# MainInterfaceBoard.net
KiCad netlist of a schematic drawn in EAGLE
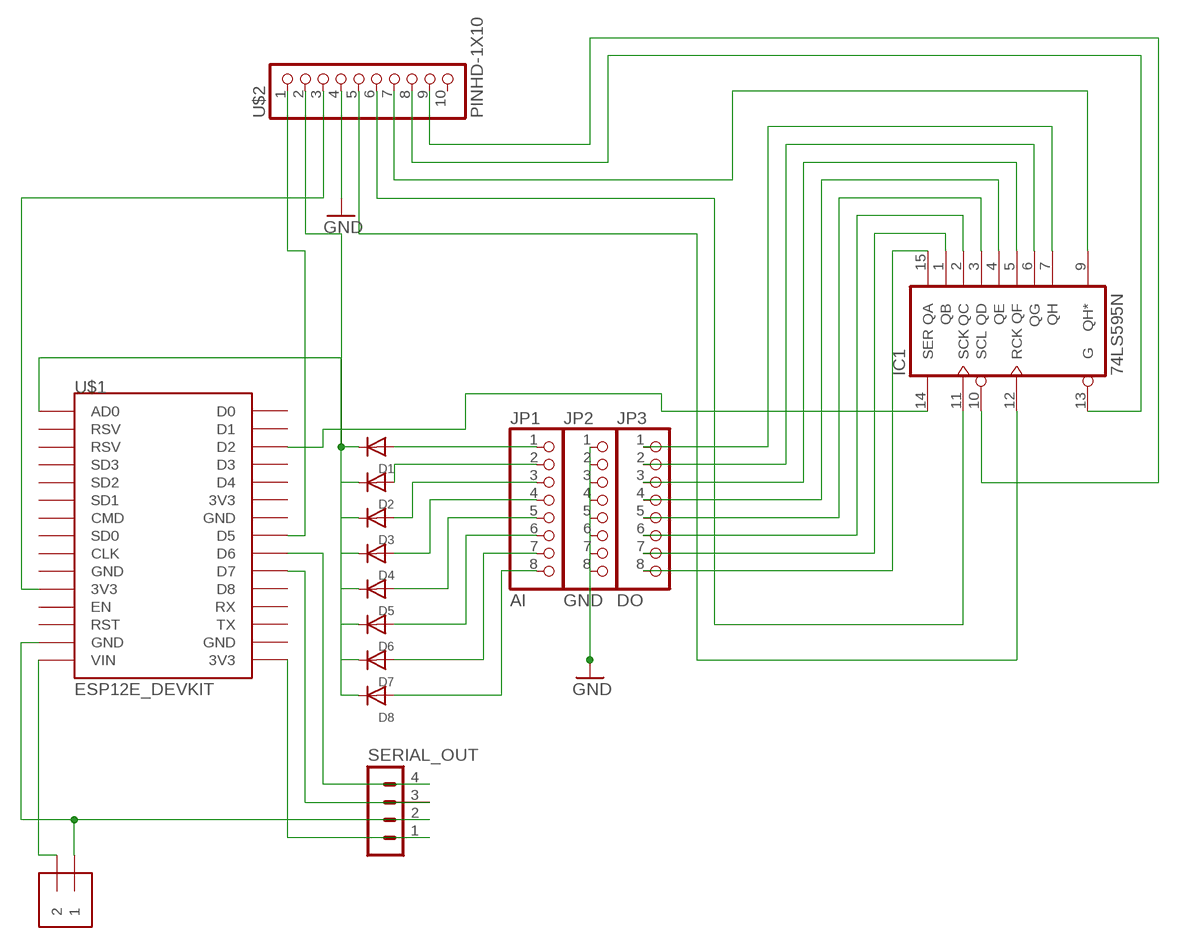
[diagram p0: schematic, sheet 1]

(export (version "E")
  (design (tool "Eeschema 10.0.6"))
  (components
    (comp (ref "D1")
      (value "DIODEDO-1N4148")
      (footprint "eagle-import:DO-1N4148")
      (libsource (lib "eagle-import") (part "DIODEDO-1N4148"))
    )
    (comp (ref "D2")
      (value "DIODEDO-1N4148")
      (footprint "eagle-import:DO-1N4148")
      (libsource (lib "eagle-import") (part "DIODEDO-1N4148"))
    )
    (comp (ref "D3")
      (value "DIODEDO-1N4148")
      (footprint "eagle-import:DO-1N4148")
      (libsource (lib "eagle-import") (part "DIODEDO-1N4148"))
    )
    (comp (ref "D4")
      (value "DIODEDO-1N4148")
      (footprint "eagle-import:DO-1N4148")
      (libsource (lib "eagle-import") (part "DIODEDO-1N4148"))
    )
    (comp (ref "D5")
      (value "DIODEDO-1N4148")
      (footprint "eagle-import:DO-1N4148")
      (libsource (lib "eagle-import") (part "DIODEDO-1N4148"))
    )
    (comp (ref "D6")
      (value "DIODEDO-1N4148")
      (footprint "eagle-import:DO-1N4148")
      (libsource (lib "eagle-import") (part "DIODEDO-1N4148"))
    )
    (comp (ref "D7")
      (value "DIODEDO-1N4148")
      (footprint "eagle-import:DO-1N4148")
      (libsource (lib "eagle-import") (part "DIODEDO-1N4148"))
    )
    (comp (ref "D8")
      (value "DIODEDO-1N4148")
      (footprint "eagle-import:DO-1N4148")
      (libsource (lib "eagle-import") (part "DIODEDO-1N4148"))
    )
    (comp (ref "IC1")
      (value "74LS595N")
      (footprint "eagle-import:DIL16")
      (libsource (lib "eagle-import") (part "74595NLS"))
    )
    (comp (ref "J2")
      (value "1X2-3.5MM")
      (footprint "eagle-import:1X2-3.5MM")
      (libsource (lib "eagle-import") (part "1X2-3.5MM"))
    )
    (comp (ref "JP1")
      (value "AI")
      (footprint "eagle-import:1X08-CLEANBIG")
      (libsource (lib "eagle-import") (part "PINHD-1X8CLEANBIG"))
    )
    (comp (ref "JP2")
      (value "GND")
      (footprint "eagle-import:1X08-CLEANBIG")
      (libsource (lib "eagle-import") (part "PINHD-1X8CLEANBIG"))
    )
    (comp (ref "JP3")
      (value "DO")
      (footprint "eagle-import:1X08-CLEANBIG")
      (libsource (lib "eagle-import") (part "PINHD-1X8CLEANBIG"))
    )
    (comp (ref "SERIAL_OUT")
      (value "MA04-1")
      (footprint "eagle-import:MA04-1")
      (libsource (lib "eagle-import") (part "MA04-1"))
    )
    (comp (ref "U$1")
      (value "ESP12E_DEVKIT")
      (footprint "eagle-import:ESP12E_DEVKIT")
      (libsource (lib "eagle-import") (part "ESP12E_DEVKIT"))
    )
    (comp (ref "U$2")
      (value "PINHD-1X10")
      (footprint "eagle-import:1X10-BIG")
      (libsource (lib "eagle-import") (part "PINHD-1X10"))
    )
  )
  (nets
    (net (code "1") (name "GND") (class "Default")
      (node (ref "JP2") (pin "1") (pinfunction "1_1") (pintype "passive"))
      (node (ref "JP2") (pin "2") (pinfunction "2_2") (pintype "passive"))
      (node (ref "JP2") (pin "3") (pinfunction "3_3") (pintype "passive"))
      (node (ref "JP2") (pin "4") (pinfunction "4_4") (pintype "passive"))
      (node (ref "JP2") (pin "5") (pinfunction "5_5") (pintype "passive"))
      (node (ref "JP2") (pin "6") (pinfunction "6_6") (pintype "passive"))
      (node (ref "JP2") (pin "7") (pinfunction "7_7") (pintype "passive"))
      (node (ref "JP2") (pin "8") (pinfunction "8_8") (pintype "passive"))
      (node (ref "U$2") (pin "4") (pinfunction "4_4") (pintype "passive"))
    )
    (net (code "2") (name "Net-(D1-PadA)") (class "Default")
      (node (ref "D1") (pin "A") (pinfunction "A_A") (pintype "passive"))
      (node (ref "JP1") (pin "1") (pinfunction "1_1") (pintype "passive"))
    )
    (net (code "3") (name "Net-(D1-PadC)") (class "Default")
      (node (ref "D1") (pin "C") (pinfunction "C_C") (pintype "passive"))
      (node (ref "D2") (pin "C") (pinfunction "C_C") (pintype "passive"))
      (node (ref "D3") (pin "C") (pinfunction "C_C") (pintype "passive"))
      (node (ref "D4") (pin "C") (pinfunction "C_C") (pintype "passive"))
      (node (ref "D5") (pin "C") (pinfunction "C_C") (pintype "passive"))
      (node (ref "D6") (pin "C") (pinfunction "C_C") (pintype "passive"))
      (node (ref "D7") (pin "C") (pinfunction "C_C") (pintype "passive"))
      (node (ref "D8") (pin "C") (pinfunction "C_C") (pintype "passive"))
      (node (ref "U$1") (pin "AD0") (pinfunction "AD0_AD0") (pintype "bidirectional"))
      (node (ref "U$2") (pin "2") (pinfunction "2_2") (pintype "passive"))
    )
    (net (code "4") (name "Net-(D2-PadA)") (class "Default")
      (node (ref "D2") (pin "A") (pinfunction "A_A") (pintype "passive"))
      (node (ref "JP1") (pin "2") (pinfunction "2_2") (pintype "passive"))
    )
    (net (code "5") (name "Net-(D3-PadA)") (class "Default")
      (node (ref "D3") (pin "A") (pinfunction "A_A") (pintype "passive"))
      (node (ref "JP1") (pin "3") (pinfunction "3_3") (pintype "passive"))
    )
    (net (code "6") (name "Net-(D4-PadA)") (class "Default")
      (node (ref "D4") (pin "A") (pinfunction "A_A") (pintype "passive"))
      (node (ref "JP1") (pin "4") (pinfunction "4_4") (pintype "passive"))
    )
    (net (code "7") (name "Net-(D5-PadA)") (class "Default")
      (node (ref "D5") (pin "A") (pinfunction "A_A") (pintype "passive"))
      (node (ref "JP1") (pin "5") (pinfunction "5_5") (pintype "passive"))
    )
    (net (code "8") (name "Net-(D6-PadA)") (class "Default")
      (node (ref "D6") (pin "A") (pinfunction "A_A") (pintype "passive"))
      (node (ref "JP1") (pin "6") (pinfunction "6_6") (pintype "passive"))
    )
    (net (code "9") (name "Net-(D7-PadA)") (class "Default")
      (node (ref "D7") (pin "A") (pinfunction "A_A") (pintype "passive"))
      (node (ref "JP1") (pin "7") (pinfunction "7_7") (pintype "passive"))
    )
    (net (code "10") (name "Net-(D8-PadA)") (class "Default")
      (node (ref "D8") (pin "A") (pinfunction "A_A") (pintype "passive"))
      (node (ref "JP1") (pin "8") (pinfunction "8_8") (pintype "passive"))
    )
    (net (code "11") (name "Net-(IC1A-G)") (class "Default")
      (node (ref "IC1") (pin "13") (pinfunction "G_13") (pintype "input"))
      (node (ref "U$2") (pin "8") (pinfunction "8_8") (pintype "passive"))
    )
    (net (code "12") (name "Net-(IC1A-QA)") (class "Default")
      (node (ref "IC1") (pin "15") (pinfunction "QA_15") (pintype "tri_state"))
      (node (ref "JP3") (pin "8") (pinfunction "8_8") (pintype "passive"))
    )
    (net (code "13") (name "Net-(IC1A-QB)") (class "Default")
      (node (ref "IC1") (pin "1") (pinfunction "QB_1") (pintype "tri_state"))
      (node (ref "JP3") (pin "7") (pinfunction "7_7") (pintype "passive"))
    )
    (net (code "14") (name "Net-(IC1A-QC)") (class "Default")
      (node (ref "IC1") (pin "2") (pinfunction "QC_2") (pintype "tri_state"))
      (node (ref "JP3") (pin "6") (pinfunction "6_6") (pintype "passive"))
    )
    (net (code "15") (name "Net-(IC1A-QD)") (class "Default")
      (node (ref "IC1") (pin "3") (pinfunction "QD_3") (pintype "tri_state"))
      (node (ref "JP3") (pin "5") (pinfunction "5_5") (pintype "passive"))
    )
    (net (code "16") (name "Net-(IC1A-QE)") (class "Default")
      (node (ref "IC1") (pin "4") (pinfunction "QE_4") (pintype "tri_state"))
      (node (ref "JP3") (pin "4") (pinfunction "4_4") (pintype "passive"))
    )
    (net (code "17") (name "Net-(IC1A-QF)") (class "Default")
      (node (ref "IC1") (pin "5") (pinfunction "QF_5") (pintype "tri_state"))
      (node (ref "JP3") (pin "3") (pinfunction "3_3") (pintype "passive"))
    )
    (net (code "18") (name "Net-(IC1A-QG)") (class "Default")
      (node (ref "IC1") (pin "6") (pinfunction "QG_6") (pintype "tri_state"))
      (node (ref "JP3") (pin "2") (pinfunction "2_2") (pintype "passive"))
    )
    (net (code "19") (name "Net-(IC1A-QH)") (class "Default")
      (node (ref "IC1") (pin "7") (pinfunction "QH_7") (pintype "tri_state"))
      (node (ref "JP3") (pin "1") (pinfunction "1_1") (pintype "passive"))
    )
    (net (code "20") (name "Net-(IC1A-QH*)") (class "Default")
      (node (ref "IC1") (pin "9") (pinfunction "QH*_9") (pintype "tri_state"))
      (node (ref "U$2") (pin "7") (pinfunction "7_7") (pintype "passive"))
    )
    (net (code "21") (name "Net-(IC1A-RCK)") (class "Default")
      (node (ref "IC1") (pin "12") (pinfunction "RCK_12") (pintype "input"))
      (node (ref "U$2") (pin "5") (pinfunction "5_5") (pintype "passive"))
    )
    (net (code "22") (name "Net-(IC1A-SCK)") (class "Default")
      (node (ref "IC1") (pin "11") (pinfunction "SCK_11") (pintype "input"))
      (node (ref "U$2") (pin "6") (pinfunction "6_6") (pintype "passive"))
    )
    (net (code "23") (name "Net-(IC1A-SCL)") (class "Default")
      (node (ref "IC1") (pin "10") (pinfunction "SCL_10") (pintype "input"))
      (node (ref "U$2") (pin "9") (pinfunction "9_9") (pintype "passive"))
    )
    (net (code "24") (name "Net-(IC1A-SER)") (class "Default")
      (node (ref "IC1") (pin "14") (pinfunction "SER_14") (pintype "input"))
      (node (ref "U$1") (pin "D2") (pinfunction "D2_D2") (pintype "bidirectional"))
    )
    (net (code "25") (name "Net-(J2-Pad1)") (class "Default")
      (node (ref "J2") (pin "1") (pinfunction "1_1") (pintype "passive"))
      (node (ref "SERIAL_OUT") (pin "2") (pinfunction "2_2") (pintype "passive"))
      (node (ref "U$1") (pin "GND@1") (pinfunction "GND_GND@1") (pintype "bidirectional"))
    )
    (net (code "26") (name "Net-(J2-Pad2)") (class "Default")
      (node (ref "J2") (pin "2") (pinfunction "2_2") (pintype "passive"))
      (node (ref "U$1") (pin "VIN") (pinfunction "VIN_VIN") (pintype "bidirectional"))
    )
    (net (code "27") (name "Net-(SERIAL_OUT-Pad1)") (class "Default")
      (node (ref "SERIAL_OUT") (pin "1") (pinfunction "1_1") (pintype "passive"))
      (node (ref "U$1") (pin "3V3@2") (pinfunction "3V3_3V3@2") (pintype "bidirectional"))
    )
    (net (code "28") (name "Net-(SERIAL_OUT-Pad3)") (class "Default")
      (node (ref "SERIAL_OUT") (pin "3") (pinfunction "3_3") (pintype "passive"))
      (node (ref "U$1") (pin "D7") (pinfunction "D7_D7") (pintype "bidirectional"))
    )
    (net (code "29") (name "Net-(SERIAL_OUT-Pad4)") (class "Default")
      (node (ref "SERIAL_OUT") (pin "4") (pinfunction "4_4") (pintype "passive"))
      (node (ref "U$1") (pin "D6") (pinfunction "D6_D6") (pintype "bidirectional"))
    )
    (net (code "30") (name "Net-(U$1-3V3-Pad3V3@0)") (class "Default")
      (node (ref "U$1") (pin "3V3@0") (pinfunction "3V3_3V3@0") (pintype "bidirectional"))
      (node (ref "U$2") (pin "3") (pinfunction "3_3") (pintype "passive"))
    )
    (net (code "31") (name "Net-(U$1-PadD5)") (class "Default")
      (node (ref "U$1") (pin "D5") (pinfunction "D5_D5") (pintype "bidirectional"))
      (node (ref "U$2") (pin "1") (pinfunction "1_1") (pintype "passive"))
    )
    (net (code "32") (name "unconnected-(U$1-3V3-Pad3V3@1)") (class "Default")
      (node (ref "U$1") (pin "3V3@1") (pinfunction "3V3_3V3@1") (pintype "bidirectional"))
    )
    (net (code "33") (name "unconnected-(U$1-GND-PadGND@0)") (class "Default")
      (node (ref "U$1") (pin "GND@0") (pinfunction "GND_GND@0") (pintype "bidirectional"))
    )
    (net (code "34") (name "unconnected-(U$1-GND-PadGND@2)") (class "Default")
      (node (ref "U$1") (pin "GND@2") (pinfunction "GND_GND@2") (pintype "bidirectional"))
    )
    (net (code "35") (name "unconnected-(U$1-GND-PadGND@3)") (class "Default")
      (node (ref "U$1") (pin "GND@3") (pinfunction "GND_GND@3") (pintype "bidirectional"))
    )
    (net (code "36") (name "unconnected-(U$1-PadCLK)") (class "Default")
      (node (ref "U$1") (pin "CLK") (pinfunction "CLK_CLK") (pintype "bidirectional"))
    )
    (net (code "37") (name "unconnected-(U$1-PadCMD)") (class "Default")
      (node (ref "U$1") (pin "CMD") (pinfunction "CMD_CMD") (pintype "bidirectional"))
    )
    (net (code "38") (name "unconnected-(U$1-PadD0)") (class "Default")
      (node (ref "U$1") (pin "D0") (pinfunction "D0_D0") (pintype "bidirectional"))
    )
    (net (code "39") (name "unconnected-(U$1-PadD1)") (class "Default")
      (node (ref "U$1") (pin "D1") (pinfunction "D1_D1") (pintype "bidirectional"))
    )
    (net (code "40") (name "unconnected-(U$1-PadD3)") (class "Default")
      (node (ref "U$1") (pin "D3") (pinfunction "D3_D3") (pintype "bidirectional"))
    )
    (net (code "41") (name "unconnected-(U$1-PadD4)") (class "Default")
      (node (ref "U$1") (pin "D4") (pinfunction "D4_D4") (pintype "bidirectional"))
    )
    (net (code "42") (name "unconnected-(U$1-PadD8)") (class "Default")
      (node (ref "U$1") (pin "D8") (pinfunction "D8_D8") (pintype "bidirectional"))
    )
    (net (code "43") (name "unconnected-(U$1-PadEN)") (class "Default")
      (node (ref "U$1") (pin "EN") (pinfunction "EN_EN") (pintype "bidirectional"))
    )
    (net (code "44") (name "unconnected-(U$1-PadRST)") (class "Default")
      (node (ref "U$1") (pin "RST") (pinfunction "RST_RST") (pintype "bidirectional"))
    )
    (net (code "45") (name "unconnected-(U$1-PadRX)") (class "Default")
      (node (ref "U$1") (pin "RX") (pinfunction "RX_RX") (pintype "bidirectional"))
    )
    (net (code "46") (name "unconnected-(U$1-PadSD0)") (class "Default")
      (node (ref "U$1") (pin "SD0") (pinfunction "SD0_SD0") (pintype "bidirectional"))
    )
    (net (code "47") (name "unconnected-(U$1-PadSD1)") (class "Default")
      (node (ref "U$1") (pin "SD1") (pinfunction "SD1_SD1") (pintype "bidirectional"))
    )
    (net (code "48") (name "unconnected-(U$1-PadSD2)") (class "Default")
      (node (ref "U$1") (pin "SD2") (pinfunction "SD2_SD2") (pintype "bidirectional"))
    )
    (net (code "49") (name "unconnected-(U$1-PadSD3)") (class "Default")
      (node (ref "U$1") (pin "SD3") (pinfunction "SD3_SD3") (pintype "bidirectional"))
    )
    (net (code "50") (name "unconnected-(U$1-PadTX)") (class "Default")
      (node (ref "U$1") (pin "TX") (pinfunction "TX_TX") (pintype "bidirectional"))
    )
    (net (code "51") (name "unconnected-(U$1-RSV-PadRSV@0)") (class "Default")
      (node (ref "U$1") (pin "RSV@0") (pinfunction "RSV_RSV@0") (pintype "bidirectional"))
    )
    (net (code "52") (name "unconnected-(U$1-RSV-PadRSV@1)") (class "Default")
      (node (ref "U$1") (pin "RSV@1") (pinfunction "RSV_RSV@1") (pintype "bidirectional"))
    )
    (net (code "53") (name "unconnected-(U$2-Pad10)") (class "Default")
      (node (ref "U$2") (pin "10") (pinfunction "10_10") (pintype "passive"))
    )
  )
)
